# power_supply.net
KiCad netlist of a schematic drawn in EAGLE
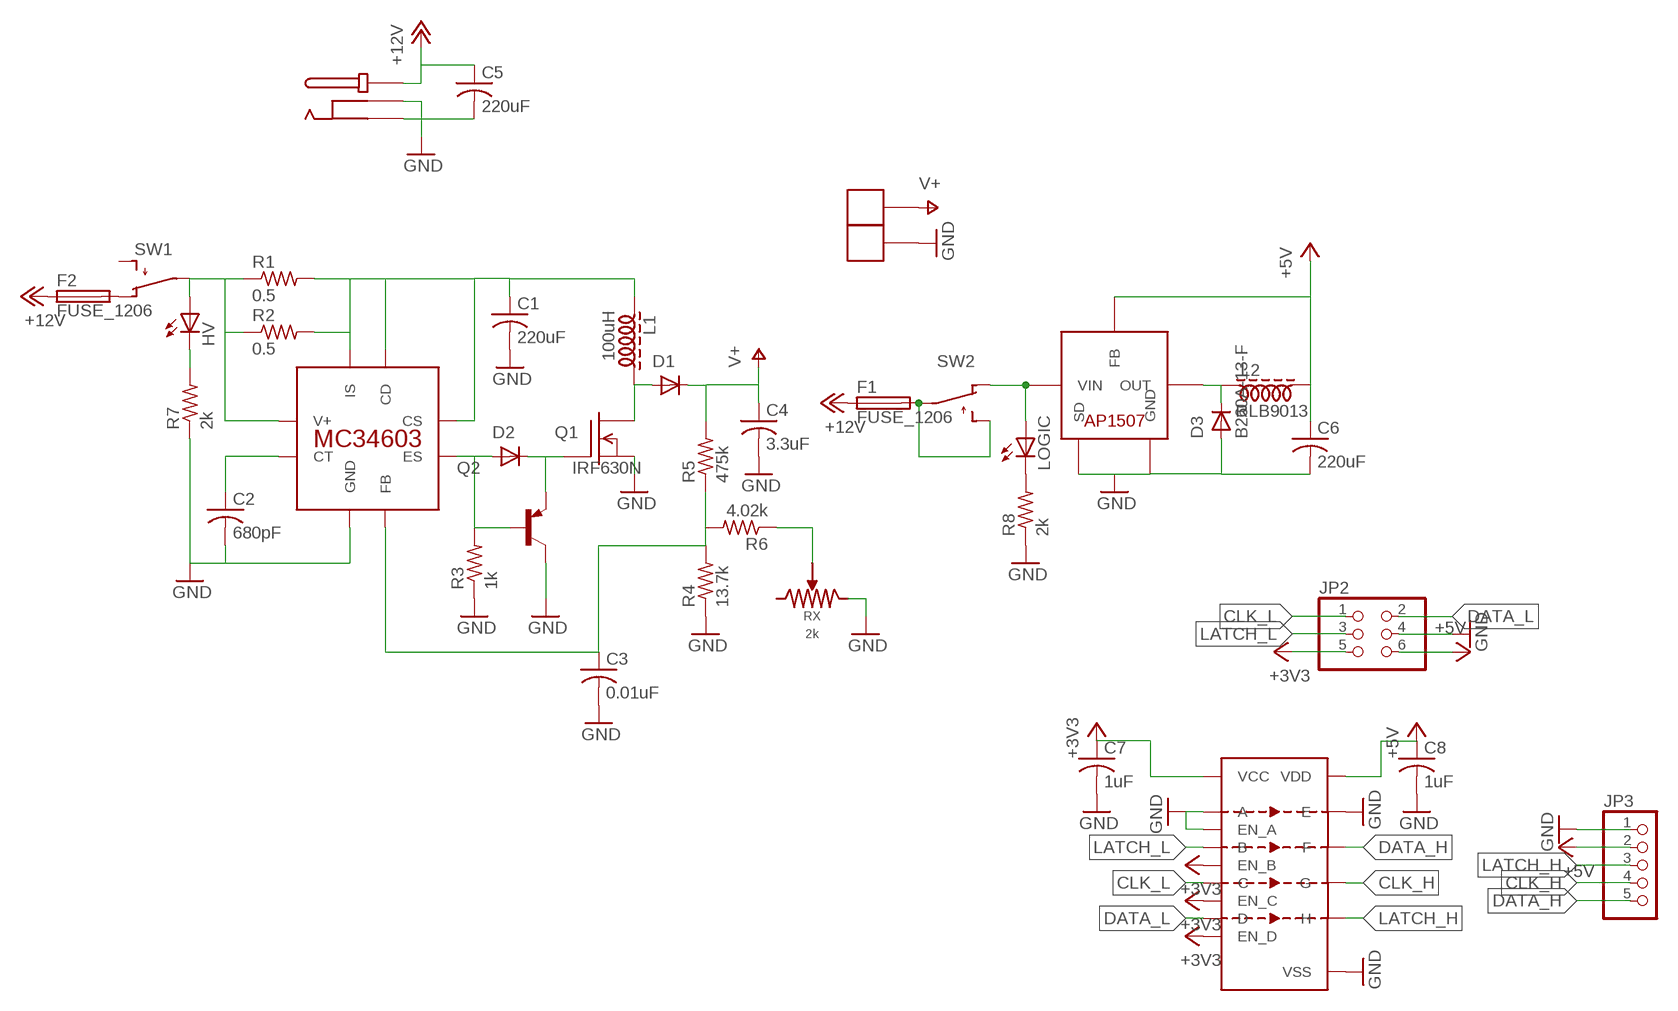
[diagram p0: schematic, sheet 1]

(export (version "E")
  (design (tool "Eeschema 10.0.6"))
  (components
    (comp (ref "C1")
      (value "220uF")
      (footprint "eagle-import:CAPAE830X1050")
      (libsource (lib "eagle-import") (part "UUR1C221MCL6GS"))
    )
    (comp (ref "C2")
      (value "680pF")
      (footprint "eagle-import:C0402")
      (libsource (lib "eagle-import") (part "C0402"))
    )
    (comp (ref "C3")
      (value "0.01uF")
      (footprint "eagle-import:C0402")
      (libsource (lib "eagle-import") (part "C0402"))
    )
    (comp (ref "C4")
      (value "3.3uF")
      (footprint "eagle-import:CAPAE830X1050")
      (libsource (lib "eagle-import") (part "UUR1C221MCL6GS"))
    )
    (comp (ref "C5")
      (value "220uF")
      (footprint "eagle-import:CAPAE830X1050")
      (libsource (lib "eagle-import") (part "UUR1C221MCL6GS"))
    )
    (comp (ref "C6")
      (value "220uF")
      (footprint "eagle-import:CAPAE830X1050")
      (libsource (lib "eagle-import") (part "UUR1C221MCL6GS"))
    )
    (comp (ref "C7")
      (value "1uF")
      (footprint "eagle-import:C0402")
      (libsource (lib "eagle-import") (part "C0402"))
    )
    (comp (ref "C8")
      (value "1uF")
      (footprint "eagle-import:C0402")
      (libsource (lib "eagle-import") (part "C0402"))
    )
    (comp (ref "D1")
      (value "BAV21W")
      (footprint "eagle-import:SOD3616X115")
      (libsource (lib "eagle-import") (part "BAV21W"))
    )
    (comp (ref "D2")
      (value "MMBD914L")
      (footprint "eagle-import:SOT23")
      (libsource (lib "eagle-import") (part "MMBD914L"))
    )
    (comp (ref "D3")
      (value "B260A-13-F")
      (footprint "eagle-import:DIOM4326X230")
      (libsource (lib "eagle-import") (part "B260A-13-F"))
    )
    (comp (ref "F1")
      (value "FUSE_1206")
      (footprint "eagle-import:R1206")
      (libsource (lib "eagle-import") (part "FUSE_1206"))
    )
    (comp (ref "F2")
      (value "FUSE_1206")
      (footprint "eagle-import:R1206")
      (libsource (lib "eagle-import") (part "FUSE_1206"))
    )
    (comp (ref "HV")
      (value "LEDCHIP-LED0805")
      (footprint "eagle-import:CHIP-LED0805")
      (libsource (lib "eagle-import") (part "LEDCHIP-LED0805"))
    )
    (comp (ref "JP2")
      (value "PINHD-2X3")
      (footprint "eagle-import:2X03")
      (libsource (lib "eagle-import") (part "PINHD-2X3"))
    )
    (comp (ref "JP3")
      (value "PINHD-1X5")
      (footprint "eagle-import:1X05")
      (libsource (lib "eagle-import") (part "PINHD-1X5"))
    )
    (comp (ref "L1")
      (value "100uH")
      (footprint "eagle-import:RLB9012")
      (libsource (lib "eagle-import") (part "RLB9012"))
    )
    (comp (ref "L2")
      (value "RLB9013")
      (footprint "eagle-import:RLB9013")
      (libsource (lib "eagle-import") (part "RLB9013"))
    )
    (comp (ref "LOGIC")
      (value "LEDCHIP-LED0805")
      (footprint "eagle-import:CHIP-LED0805")
      (libsource (lib "eagle-import") (part "LEDCHIP-LED0805"))
    )
    (comp (ref "Q1")
      (value "IRF630N")
      (footprint "eagle-import:TO254P1524X483-3")
      (libsource (lib "eagle-import") (part "IRF630N"))
    )
    (comp (ref "Q2")
      (value "BC807-16-PNP-SOT23-BEC")
      (footprint "eagle-import:SOT23-BEC")
      (libsource (lib "eagle-import") (part "-PNP-SOT23-BECBC807-16"))
    )
    (comp (ref "R1")
      (value "0.5")
      (footprint "eagle-import:R1206")
      (libsource (lib "eagle-import") (part "R-US_R1206"))
    )
    (comp (ref "R2")
      (value "0.5")
      (footprint "eagle-import:R1206")
      (libsource (lib "eagle-import") (part "R-US_R1206"))
    )
    (comp (ref "R3")
      (value "1k")
      (footprint "eagle-import:R0805")
      (libsource (lib "eagle-import") (part "R-US_R0805"))
    )
    (comp (ref "R4")
      (value "13.7k")
      (footprint "eagle-import:R1206")
      (libsource (lib "eagle-import") (part "R-US_R1206"))
    )
    (comp (ref "R5")
      (value "475k")
      (footprint "eagle-import:R1206")
      (libsource (lib "eagle-import") (part "R-US_R1206"))
    )
    (comp (ref "R6")
      (value "4.02k")
      (footprint "eagle-import:R1206")
      (libsource (lib "eagle-import") (part "R-US_R1206"))
    )
    (comp (ref "R7")
      (value "2k")
      (footprint "eagle-import:R0805")
      (libsource (lib "eagle-import") (part "R-US_R0805"))
    )
    (comp (ref "R8")
      (value "2k")
      (footprint "eagle-import:R0805")
      (libsource (lib "eagle-import") (part "R-US_R0805"))
    )
    (comp (ref "RX")
      (value "2k")
      (footprint "eagle-import:TC33X-2")
      (libsource (lib "eagle-import") (part "TC33X-2"))
    )
    (comp (ref "SW1")
      (value "T411001B")
      (footprint "eagle-import:T411001B")
      (libsource (lib "eagle-import") (part "T411001B"))
    )
    (comp (ref "SW2")
      (value "T411001B")
      (footprint "eagle-import:T411001B")
      (libsource (lib "eagle-import") (part "T411001B"))
    )
    (comp (ref "U$1")
      (value "EJ508A")
      (footprint "eagle-import:EJ508A")
      (libsource (lib "eagle-import") (part "EJ508A"))
    )
    (comp (ref "U$5")
      (value "ZKFDS")
      (footprint "eagle-import:ZKFDS")
      (libsource (lib "eagle-import") (part "ZKFDS"))
    )
    (comp (ref "U$6")
      (value "ZKFDS")
      (footprint "eagle-import:ZKFDS")
      (libsource (lib "eagle-import") (part "ZKFDS"))
    )
    (comp (ref "U1")
      (value "MC34063")
      (footprint "eagle-import:SOIC127P600X175-8")
      (libsource (lib "eagle-import") (part "MC34063"))
    )
    (comp (ref "U2")
      (value "AP1507SOIC-8")
      (footprint "eagle-import:SOIC127P600X175-8")
      (libsource (lib "eagle-import") (part "AP1507SOIC-8"))
    )
    (comp (ref "U3")
      (value "CD40109B_SPLITEN")
      (footprint "eagle-import:SOP65P640X120-16")
      (libsource (lib "eagle-import") (part "CD40109B_SPLITEN"))
    )
  )
  (nets
    (net (code "1") (name "+3V3") (class "Default")
      (node (ref "C7") (pin "1") (pinfunction "+_1") (pintype "passive"))
      (node (ref "JP2") (pin "5") (pinfunction "5_5") (pintype "passive"))
      (node (ref "U3") (pin "1") (pinfunction "VCC_1") (pintype "bidirectional"))
      (node (ref "U3") (pin "15") (pinfunction "EN_D_15") (pintype "bidirectional"))
      (node (ref "U3") (pin "7") (pinfunction "EN_B_7") (pintype "bidirectional"))
      (node (ref "U3") (pin "9") (pinfunction "EN_C_9") (pintype "bidirectional"))
    )
    (net (code "2") (name "+5V") (class "Default")
      (node (ref "C6") (pin "1") (pinfunction "+_1") (pintype "passive"))
      (node (ref "C8") (pin "1") (pinfunction "+_1") (pintype "passive"))
      (node (ref "JP2") (pin "6") (pinfunction "6_6") (pintype "passive"))
      (node (ref "JP3") (pin "2") (pinfunction "2_2") (pintype "passive"))
      (node (ref "L2") (pin "P$2") (pinfunction "2_P$2") (pintype "passive"))
      (node (ref "U2") (pin "3") (pinfunction "FB_3") (pintype "bidirectional"))
      (node (ref "U3") (pin "16") (pinfunction "VDD_16") (pintype "bidirectional"))
    )
    (net (code "3") (name "+12V") (class "Default")
      (node (ref "C5") (pin "1") (pinfunction "+_1") (pintype "passive"))
      (node (ref "F1") (pin "1") (pinfunction "1_1") (pintype "passive"))
      (node (ref "F2") (pin "1") (pinfunction "1_1") (pintype "passive"))
      (node (ref "U$1") (pin "P$1") (pinfunction "P$1_P$1") (pintype "bidirectional"))
    )
    (net (code "4") (name "CLK_H") (class "Default")
      (node (ref "JP3") (pin "4") (pinfunction "4_4") (pintype "passive"))
      (node (ref "U3") (pin "11") (pinfunction "G_11") (pintype "bidirectional"))
    )
    (net (code "5") (name "CLK_L") (class "Default")
      (node (ref "JP2") (pin "1") (pinfunction "1_1") (pintype "passive"))
      (node (ref "U3") (pin "10") (pinfunction "C_10") (pintype "bidirectional"))
    )
    (net (code "6") (name "DATA_H") (class "Default")
      (node (ref "JP3") (pin "5") (pinfunction "5_5") (pintype "passive"))
      (node (ref "U3") (pin "5") (pinfunction "F_5") (pintype "bidirectional"))
    )
    (net (code "7") (name "DATA_L") (class "Default")
      (node (ref "JP2") (pin "2") (pinfunction "2_2") (pintype "passive"))
      (node (ref "U3") (pin "14") (pinfunction "D_14") (pintype "bidirectional"))
    )
    (net (code "8") (name "GND") (class "Default")
      (node (ref "C1") (pin "2") (pinfunction "-_2") (pintype "passive"))
      (node (ref "C2") (pin "2") (pinfunction "-_2") (pintype "passive"))
      (node (ref "C3") (pin "2") (pinfunction "-_2") (pintype "passive"))
      (node (ref "C4") (pin "2") (pinfunction "-_2") (pintype "passive"))
      (node (ref "C5") (pin "2") (pinfunction "-_2") (pintype "passive"))
      (node (ref "C6") (pin "2") (pinfunction "-_2") (pintype "passive"))
      (node (ref "C7") (pin "2") (pinfunction "-_2") (pintype "passive"))
      (node (ref "C8") (pin "2") (pinfunction "-_2") (pintype "passive"))
      (node (ref "D3") (pin "2") (pinfunction "A_2") (pintype "passive"))
      (node (ref "JP2") (pin "4") (pinfunction "4_4") (pintype "passive"))
      (node (ref "JP3") (pin "1") (pinfunction "1_1") (pintype "passive"))
      (node (ref "Q1") (pin "2") (pinfunction "S_2") (pintype "passive"))
      (node (ref "Q2") (pin "C") (pinfunction "C_C") (pintype "passive"))
      (node (ref "R3") (pin "1") (pinfunction "1_1") (pintype "passive"))
      (node (ref "R4") (pin "1") (pinfunction "1_1") (pintype "passive"))
      (node (ref "R7") (pin "1") (pinfunction "1_1") (pintype "passive"))
      (node (ref "R8") (pin "1") (pinfunction "1_1") (pintype "passive"))
      (node (ref "RX") (pin "P$3") (pinfunction "P$3_P$3") (pintype "bidirectional"))
      (node (ref "U$1") (pin "P$2") (pinfunction "P$2_P$2") (pintype "bidirectional"))
      (node (ref "U$1") (pin "P$3") (pinfunction "P$3_P$3") (pintype "bidirectional"))
      (node (ref "U$6") (pin "P$1") (pinfunction "P$1_P$1") (pintype "bidirectional"))
      (node (ref "U$6") (pin "P$2") (pinfunction "P$1_P$2") (pintype "bidirectional"))
      (node (ref "U1") (pin "4") (pinfunction "GND_4") (pintype "bidirectional"))
      (node (ref "U2") (pin "4") (pinfunction "SD_4") (pintype "bidirectional"))
      (node (ref "U2") (pin "5") (pinfunction "GND_5") (pintype "bidirectional"))
      (node (ref "U2") (pin "6") (pinfunction "GND_6") (pintype "bidirectional"))
      (node (ref "U2") (pin "7") (pinfunction "GND_7") (pintype "bidirectional"))
      (node (ref "U2") (pin "8") (pinfunction "GND_8") (pintype "bidirectional"))
      (node (ref "U3") (pin "12") (pinfunction "VSS_12") (pintype "bidirectional"))
      (node (ref "U3") (pin "2") (pinfunction "EN_A_2") (pintype "bidirectional"))
      (node (ref "U3") (pin "3") (pinfunction "A_3") (pintype "bidirectional"))
      (node (ref "U3") (pin "4") (pinfunction "E_4") (pintype "bidirectional"))
      (node (ref "U3") (pin "8") (pinfunction "VSS_8") (pintype "bidirectional"))
    )
    (net (code "9") (name "LATCH_H") (class "Default")
      (node (ref "JP3") (pin "3") (pinfunction "3_3") (pintype "passive"))
      (node (ref "U3") (pin "13") (pinfunction "H_13") (pintype "bidirectional"))
    )
    (net (code "10") (name "LATCH_L") (class "Default")
      (node (ref "JP2") (pin "3") (pinfunction "3_3") (pintype "passive"))
      (node (ref "U3") (pin "6") (pinfunction "B_6") (pintype "bidirectional"))
    )
    (net (code "11") (name "Net-(C1-+)") (class "Default")
      (node (ref "C1") (pin "1") (pinfunction "+_1") (pintype "passive"))
      (node (ref "L1") (pin "P$1") (pinfunction "1_P$1") (pintype "passive"))
      (node (ref "R1") (pin "2") (pinfunction "2_2") (pintype "passive"))
      (node (ref "R2") (pin "2") (pinfunction "2_2") (pintype "passive"))
      (node (ref "U1") (pin "1") (pinfunction "CS_1") (pintype "bidirectional"))
      (node (ref "U1") (pin "7") (pinfunction "IS_7") (pintype "bidirectional"))
      (node (ref "U1") (pin "8") (pinfunction "CD_8") (pintype "bidirectional"))
    )
    (net (code "12") (name "Net-(C2-+)") (class "Default")
      (node (ref "C2") (pin "1") (pinfunction "+_1") (pintype "passive"))
      (node (ref "U1") (pin "3") (pinfunction "CT_3") (pintype "bidirectional"))
    )
    (net (code "13") (name "Net-(C3-+)") (class "Default")
      (node (ref "C3") (pin "1") (pinfunction "+_1") (pintype "passive"))
      (node (ref "R4") (pin "2") (pinfunction "2_2") (pintype "passive"))
      (node (ref "R5") (pin "1") (pinfunction "1_1") (pintype "passive"))
      (node (ref "R6") (pin "2") (pinfunction "2_2") (pintype "passive"))
      (node (ref "U1") (pin "5") (pinfunction "FB_5") (pintype "bidirectional"))
    )
    (net (code "14") (name "Net-(D1-A)") (class "Default")
      (node (ref "D1") (pin "1") (pinfunction "A_1") (pintype "passive"))
      (node (ref "L1") (pin "P$2") (pinfunction "2_P$2") (pintype "passive"))
      (node (ref "Q1") (pin "3") (pinfunction "D_3") (pintype "passive"))
    )
    (net (code "15") (name "Net-(D2-A)") (class "Default")
      (node (ref "D2") (pin "1") (pinfunction "A_1") (pintype "passive"))
      (node (ref "Q2") (pin "B") (pinfunction "B_B") (pintype "passive"))
      (node (ref "R3") (pin "2") (pinfunction "2_2") (pintype "passive"))
      (node (ref "U1") (pin "2") (pinfunction "ES_2") (pintype "bidirectional"))
    )
    (net (code "16") (name "Net-(D2-C)") (class "Default")
      (node (ref "D2") (pin "3") (pinfunction "C_3") (pintype "passive"))
      (node (ref "Q1") (pin "1") (pinfunction "G_1") (pintype "passive"))
      (node (ref "Q2") (pin "E") (pinfunction "E_E") (pintype "passive"))
    )
    (net (code "17") (name "Net-(D3-C)") (class "Default")
      (node (ref "D3") (pin "1") (pinfunction "C_1") (pintype "passive"))
      (node (ref "L2") (pin "P$1") (pinfunction "1_P$1") (pintype "passive"))
      (node (ref "U2") (pin "2") (pinfunction "OUT_2") (pintype "bidirectional"))
    )
    (net (code "18") (name "Net-(HV-PadC)") (class "Default")
      (node (ref "HV") (pin "C") (pinfunction "C_C") (pintype "passive"))
      (node (ref "R7") (pin "2") (pinfunction "2_2") (pintype "passive"))
    )
    (net (code "19") (name "Net-(LOGIC-PadC)") (class "Default")
      (node (ref "LOGIC") (pin "C") (pinfunction "C_C") (pintype "passive"))
      (node (ref "R8") (pin "2") (pinfunction "2_2") (pintype "passive"))
    )
    (net (code "20") (name "Net-(R6-Pad1)") (class "Default")
      (node (ref "R6") (pin "1") (pinfunction "1_1") (pintype "passive"))
      (node (ref "RX") (pin "P$2") (pinfunction "P$2_P$2") (pintype "bidirectional"))
    )
    (net (code "21") (name "Net-(SW1-1)") (class "Default")
      (node (ref "F2") (pin "2") (pinfunction "2_2") (pintype "passive"))
      (node (ref "SW1") (pin "P$1") (pinfunction "1_P$1") (pintype "passive"))
    )
    (net (code "22") (name "Net-(SW1-2)") (class "Default")
      (node (ref "HV") (pin "A") (pinfunction "A_A") (pintype "passive"))
      (node (ref "R1") (pin "1") (pinfunction "1_1") (pintype "passive"))
      (node (ref "R2") (pin "1") (pinfunction "1_1") (pintype "passive"))
      (node (ref "SW1") (pin "P$2") (pinfunction "2_P$2") (pintype "passive"))
      (node (ref "U1") (pin "6") (pinfunction "V+_6") (pintype "bidirectional"))
    )
    (net (code "23") (name "Net-(SW2-1)") (class "Default")
      (node (ref "LOGIC") (pin "A") (pinfunction "A_A") (pintype "passive"))
      (node (ref "SW2") (pin "P$1") (pinfunction "1_P$1") (pintype "passive"))
      (node (ref "U2") (pin "1") (pinfunction "VIN_1") (pintype "bidirectional"))
    )
    (net (code "24") (name "Net-(SW2-2)") (class "Default")
      (node (ref "F1") (pin "2") (pinfunction "2_2") (pintype "passive"))
      (node (ref "SW2") (pin "P$2") (pinfunction "2_P$2") (pintype "passive"))
      (node (ref "SW2") (pin "P$3") (pinfunction "3_P$3") (pintype "passive"))
    )
    (net (code "25") (name "V+") (class "Default")
      (node (ref "C4") (pin "1") (pinfunction "+_1") (pintype "passive"))
      (node (ref "D1") (pin "2") (pinfunction "C_2") (pintype "passive"))
      (node (ref "R5") (pin "2") (pinfunction "2_2") (pintype "passive"))
      (node (ref "U$5") (pin "P$1") (pinfunction "P$1_P$1") (pintype "bidirectional"))
      (node (ref "U$5") (pin "P$2") (pinfunction "P$1_P$2") (pintype "bidirectional"))
    )
    (net (code "26") (name "unconnected-(RX-PadP$1)") (class "Default")
      (node (ref "RX") (pin "P$1") (pinfunction "P$1_P$1") (pintype "bidirectional"))
    )
    (net (code "27") (name "unconnected-(SW1-3-PadP$3)") (class "Default")
      (node (ref "SW1") (pin "P$3") (pinfunction "3_P$3") (pintype "passive"))
    )
  )
)
